# LTE.net
KiCad netlist of a schematic drawn in Altium Designer
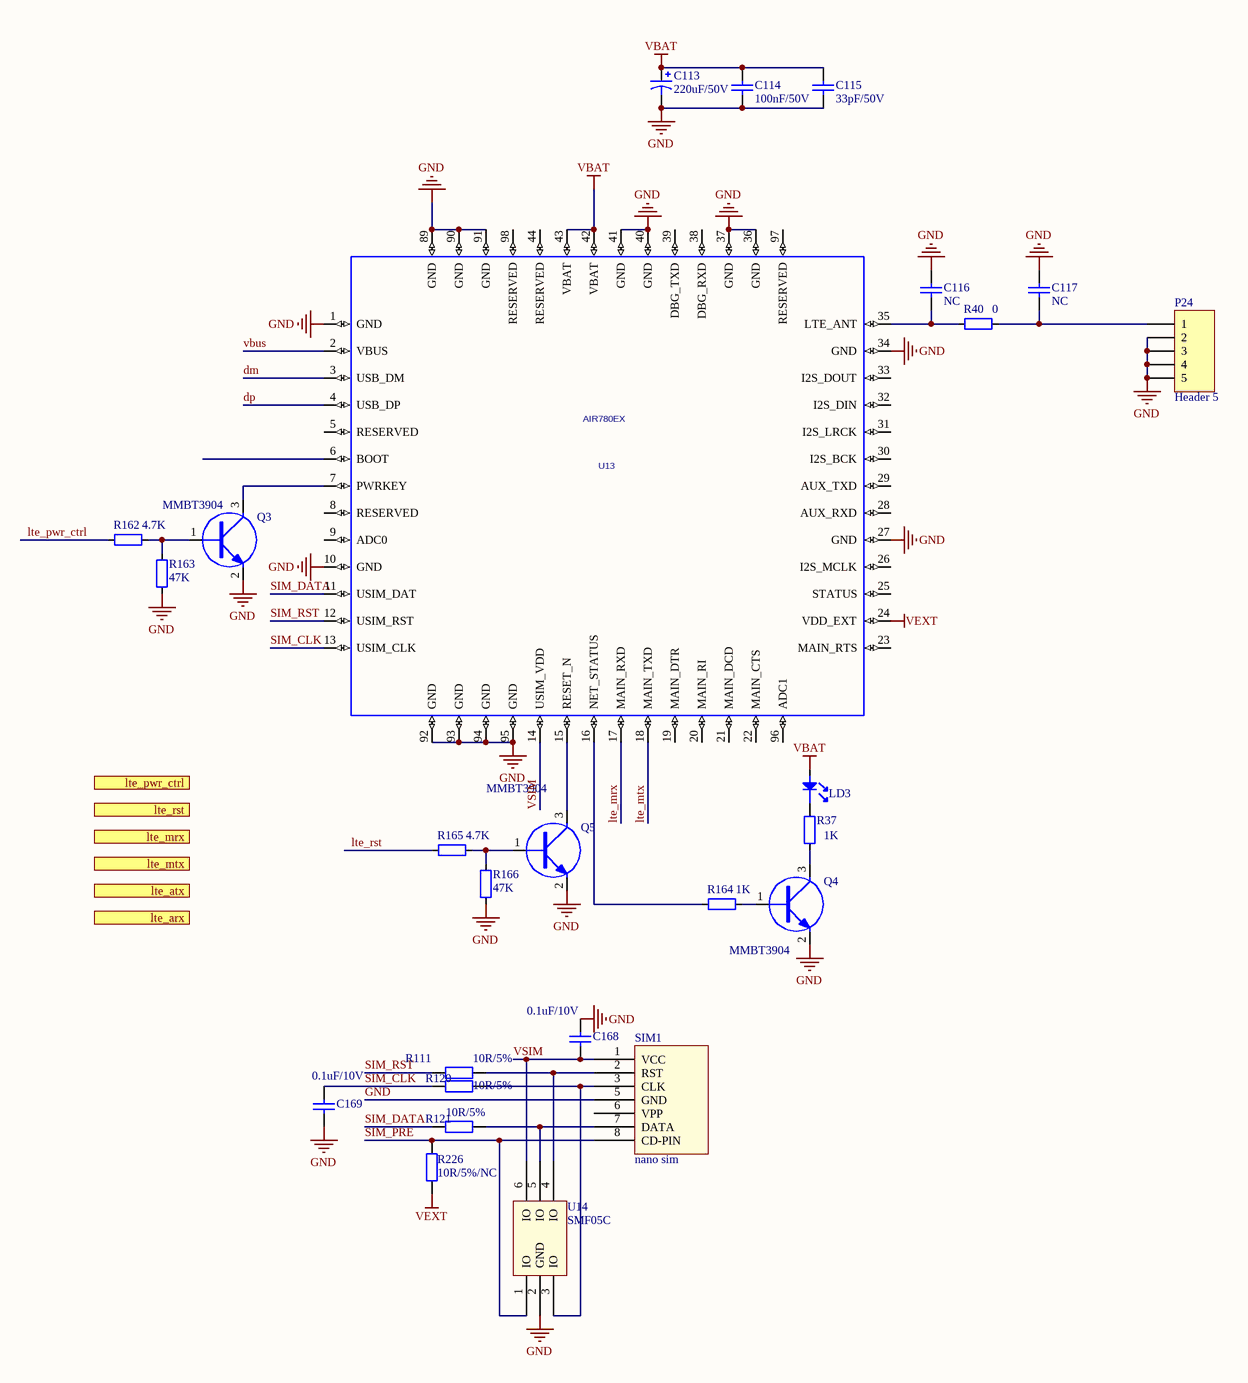
[diagram p0: LTE.SchDoc]

(export (version "E")
  (design (tool "Eeschema 10.0.6"))
  (components
    (comp (ref "C113")
      (value "220uF/50V")
      (footprint "Φ10×10")
      (description "Polarized Capacitor (Radial)")
      (fields (field (name "PUBLISHER") "Altium Limited"))
      (libsource (lib "Miscellaneous Devices") (part "Cap Pol1"))
    )
    (comp (ref "C114")
      (value "100nF/50V")
      (footprint "0603C")
      (description "Capacitor")
      (fields (field (name "PUBLISHER") "Altium Limited"))
      (libsource (lib "Miscellaneous Devices") (part "Cap"))
    )
    (comp (ref "C115")
      (value "33pF/50V")
      (footprint "0603C")
      (description "Capacitor")
      (fields (field (name "PUBLISHER") "Altium Limited"))
      (libsource (lib "Miscellaneous Devices") (part "Cap"))
    )
    (comp (ref "C116")
      (value "NC")
      (footprint "0603c")
      (description "Capacitor")
      (fields (field (name "PUBLISHER") "Altium Limited"))
      (libsource (lib "Miscellaneous Devices") (part "Cap"))
    )
    (comp (ref "C117")
      (value "NC")
      (footprint "0603c")
      (description "Capacitor")
      (fields (field (name "PUBLISHER") "Altium Limited"))
      (libsource (lib "Miscellaneous Devices") (part "Cap"))
    )
    (comp (ref "C168")
      (value "0.1uF/10V")
      (footprint "0603c")
      (description "Capacitor")
      (fields (field (name "PUBLISHER") "Altium Limited"))
      (libsource (lib "Miscellaneous Devices") (part "Cap"))
    )
    (comp (ref "C169")
      (value "0.1uF/10V")
      (footprint "0603c")
      (description "Capacitor")
      (fields (field (name "PUBLISHER") "Altium Limited"))
      (libsource (lib "Miscellaneous Devices") (part "Cap"))
    )
    (comp (ref "LD3")
      (value "LED_Green_19-217")
      (footprint "0603led")
      (libsource (lib "RC_M_D_00") (part "LED_Green_19-217"))
    )
    (comp (ref "P24")
      (value "Header 5")
      (footprint "KH-SMA-KE-Z")
      (description "Header, 5-Pin")
      (fields (field (name "PUBLISHER") "Altium Limited"))
      (libsource (lib "Miscellaneous Connectors") (part "Header 5"))
    )
    (comp (ref "Q3")
      (value "MMBT3904")
      (footprint "SOT23-3")
      (libsource (lib "CenLib") (part "NPN_MMBT3904"))
    )
    (comp (ref "Q4")
      (value "MMBT3904")
      (footprint "SOT23-3")
      (libsource (lib "CenLib") (part "NPN_MMBT3904"))
    )
    (comp (ref "Q5")
      (value "MMBT3904")
      (footprint "SOT23-3")
      (libsource (lib "CenLib") (part "NPN_MMBT3904"))
    )
    (comp (ref "R37") (value "1K") (footprint "0603R") (libsource (lib "RC_M_D_00") (part "RES0603")))
    (comp (ref "R40") (value "0") (footprint "0603r") (libsource (lib "RC_M_D_00") (part "RES0603")))
    (comp (ref "R111")
      (value "10R/5%")
      (footprint "0603r")
      (description "Resistor")
      (fields (field (name "PUBLISHER") "Altium Limited"))
      (libsource (lib "Miscellaneous Devices") (part "Res2"))
    )
    (comp (ref "R120")
      (value "10R/5%")
      (footprint "0603r")
      (description "Resistor")
      (fields (field (name "PUBLISHER") "Altium Limited"))
      (libsource (lib "Miscellaneous Devices") (part "Res2"))
    )
    (comp (ref "R121")
      (value "10R/5%")
      (footprint "0603r")
      (description "Resistor")
      (fields (field (name "PUBLISHER") "Altium Limited"))
      (libsource (lib "Miscellaneous Devices") (part "Res2"))
    )
    (comp (ref "R162") (value "4.7K") (footprint "0603R") (libsource (lib "RC_M_D_00") (part "RES0603")))
    (comp (ref "R163") (value "47K") (footprint "0603r") (libsource (lib "RC_M_D_00") (part "RES0603")))
    (comp (ref "R164") (value "1K") (footprint "0603r") (libsource (lib "RC_M_D_00") (part "RES0603")))
    (comp (ref "R165") (value "4.7K") (footprint "0603R") (libsource (lib "RC_M_D_00") (part "RES0603")))
    (comp (ref "R166") (value "47K") (footprint "0603r") (libsource (lib "RC_M_D_00") (part "RES0603")))
    (comp (ref "R226")
      (value "10R/5%/NC")
      (footprint "0603r")
      (description "Resistor")
      (fields (field (name "PUBLISHER") "Altium Limited"))
      (libsource (lib "") (part "Res2_1"))
    )
    (comp (ref "SIM1") (value "nano sim") (footprint "Nano SIM") (libsource (lib "lm") (part "nano sim")))
    (comp (ref "U13")
      (value "AIR780EX")
      (footprint "Air780EX_AD:AIR780EX")
      (libsource (lib "*") (part "AIR780EX"))
    )
    (comp (ref "U14") (value "SMF05C") (footprint "sc70-6l") (libsource (lib "lm") (part "SMF05C")))
  )
  (nets
    (net (code "1") (name "/SIM_CLK") (class "Default")
      (node (ref "C169") (pin "1") (pinfunction "1_1") (pintype "passive"))
      (node (ref "R120") (pin "2") (pinfunction "2_2") (pintype "passive"))
      (node (ref "U13") (pin "13") (pinfunction "USIM_CLK_13") (pintype "bidirectional"))
    )
    (net (code "2") (name "/SIM_DATA") (class "Default")
      (node (ref "R121") (pin "2") (pinfunction "2_2") (pintype "passive"))
      (node (ref "U13") (pin "11") (pinfunction "USIM_DAT_11") (pintype "bidirectional"))
    )
    (net (code "3") (name "/SIM_PRE") (class "Default")
      (node (ref "R226") (pin "1") (pinfunction "1_1") (pintype "passive"))
      (node (ref "SIM1") (pin "8") (pinfunction "CD-PIN_8") (pintype "passive"))
      (node (ref "U14") (pin "1") (pinfunction "IO_1") (pintype "passive"))
    )
    (net (code "4") (name "/SIM_RST") (class "Default")
      (node (ref "R111") (pin "2") (pinfunction "2_2") (pintype "passive"))
      (node (ref "U13") (pin "12") (pinfunction "USIM_RST_12") (pintype "bidirectional"))
    )
    (net (code "5") (name "/VSIM") (class "Default")
      (node (ref "C168") (pin "2") (pinfunction "2_2") (pintype "passive"))
      (node (ref "SIM1") (pin "1") (pinfunction "VCC_1") (pintype "passive"))
      (node (ref "U13") (pin "14") (pinfunction "USIM_VDD_14") (pintype "bidirectional"))
      (node (ref "U14") (pin "6") (pinfunction "IO_6") (pintype "passive"))
    )
    (net (code "6") (name "/dm") (class "Default")
      (node (ref "U13") (pin "3") (pinfunction "USB_DM_3") (pintype "bidirectional"))
    )
    (net (code "7") (name "/dp") (class "Default")
      (node (ref "U13") (pin "4") (pinfunction "USB_DP_4") (pintype "bidirectional"))
    )
    (net (code "10") (name "/lte_mrx") (class "Default")
      (node (ref "U13") (pin "17") (pinfunction "MAIN_RXD_17") (pintype "bidirectional"))
    )
    (net (code "11") (name "/lte_mtx") (class "Default")
      (node (ref "U13") (pin "18") (pinfunction "MAIN_TXD_18") (pintype "bidirectional"))
    )
    (net (code "12") (name "/lte_pwr_ctrl") (class "Default")
      (node (ref "R162") (pin "1") (pinfunction "1_1") (pintype "passive"))
    )
    (net (code "13") (name "/lte_rst") (class "Default")
      (node (ref "R165") (pin "1") (pinfunction "1_1") (pintype "passive"))
    )
    (net (code "14") (name "/vbus") (class "Default")
      (node (ref "U13") (pin "2") (pinfunction "VBUS_2") (pintype "bidirectional"))
    )
    (net (code "15") (name "GND") (class "Default")
      (node (ref "C113") (pin "2") (pinfunction "2_2") (pintype "passive"))
      (node (ref "C114") (pin "1") (pinfunction "1_1") (pintype "passive"))
      (node (ref "C115") (pin "1") (pinfunction "1_1") (pintype "passive"))
      (node (ref "C116") (pin "2") (pinfunction "2_2") (pintype "passive"))
      (node (ref "C117") (pin "2") (pinfunction "2_2") (pintype "passive"))
      (node (ref "C168") (pin "1") (pinfunction "1_1") (pintype "passive"))
      (node (ref "C169") (pin "2") (pinfunction "2_2") (pintype "passive"))
      (node (ref "P24") (pin "2") (pinfunction "2_2") (pintype "passive"))
      (node (ref "P24") (pin "3") (pinfunction "3_3") (pintype "passive"))
      (node (ref "P24") (pin "4") (pinfunction "4_4") (pintype "passive"))
      (node (ref "P24") (pin "5") (pinfunction "5_5") (pintype "passive"))
      (node (ref "Q3") (pin "2") (pinfunction "E_2") (pintype "passive"))
      (node (ref "Q4") (pin "2") (pinfunction "E_2") (pintype "passive"))
      (node (ref "Q5") (pin "2") (pinfunction "E_2") (pintype "passive"))
      (node (ref "R163") (pin "1") (pinfunction "1_1") (pintype "passive"))
      (node (ref "R166") (pin "1") (pinfunction "1_1") (pintype "passive"))
      (node (ref "SIM1") (pin "5") (pinfunction "GND_5") (pintype "passive"))
      (node (ref "U13") (pin "1") (pinfunction "GND_1") (pintype "bidirectional"))
      (node (ref "U13") (pin "10") (pinfunction "GND_10") (pintype "bidirectional"))
      (node (ref "U13") (pin "27") (pinfunction "GND_27") (pintype "bidirectional"))
      (node (ref "U13") (pin "34") (pinfunction "GND_34") (pintype "bidirectional"))
      (node (ref "U13") (pin "36") (pinfunction "GND_36") (pintype "bidirectional"))
      (node (ref "U13") (pin "37") (pinfunction "GND_37") (pintype "bidirectional"))
      (node (ref "U13") (pin "40") (pinfunction "GND_40") (pintype "bidirectional"))
      (node (ref "U13") (pin "41") (pinfunction "GND_41") (pintype "bidirectional"))
      (node (ref "U13") (pin "89") (pinfunction "GND_89") (pintype "bidirectional"))
      (node (ref "U13") (pin "90") (pinfunction "GND_90") (pintype "bidirectional"))
      (node (ref "U13") (pin "91") (pinfunction "GND_91") (pintype "bidirectional"))
      (node (ref "U13") (pin "92") (pinfunction "GND_92") (pintype "bidirectional"))
      (node (ref "U13") (pin "93") (pinfunction "GND_93") (pintype "bidirectional"))
      (node (ref "U13") (pin "94") (pinfunction "GND_94") (pintype "bidirectional"))
      (node (ref "U13") (pin "95") (pinfunction "GND_95") (pintype "bidirectional"))
      (node (ref "U14") (pin "2") (pinfunction "GND_2") (pintype "passive"))
    )
    (net (code "16") (name "Net-(C117-Pad1)") (class "Default")
      (node (ref "C117") (pin "1") (pinfunction "1_1") (pintype "passive"))
      (node (ref "P24") (pin "1") (pinfunction "1_1") (pintype "passive"))
      (node (ref "R40") (pin "2") (pinfunction "2_2") (pintype "passive"))
    )
    (net (code "17") (name "Net-(LD3-Pad2)") (class "Default")
      (node (ref "LD3") (pin "2") (pinfunction "2_2") (pintype "passive"))
      (node (ref "R37") (pin "1") (pinfunction "1_1") (pintype "passive"))
    )
    (net (code "18") (name "Net-(Q3-B)") (class "Default")
      (node (ref "Q3") (pin "1") (pinfunction "B_1") (pintype "passive"))
      (node (ref "R162") (pin "2") (pinfunction "2_2") (pintype "passive"))
      (node (ref "R163") (pin "2") (pinfunction "2_2") (pintype "passive"))
    )
    (net (code "19") (name "Net-(Q3-C)") (class "Default")
      (node (ref "Q3") (pin "3") (pinfunction "C_3") (pintype "passive"))
      (node (ref "U13") (pin "7") (pinfunction "PWRKEY_7") (pintype "bidirectional"))
    )
    (net (code "20") (name "Net-(Q4-B)") (class "Default")
      (node (ref "Q4") (pin "1") (pinfunction "B_1") (pintype "passive"))
      (node (ref "R164") (pin "2") (pinfunction "2_2") (pintype "passive"))
    )
    (net (code "21") (name "Net-(Q4-C)") (class "Default")
      (node (ref "Q4") (pin "3") (pinfunction "C_3") (pintype "passive"))
      (node (ref "R37") (pin "2") (pinfunction "2_2") (pintype "passive"))
    )
    (net (code "22") (name "Net-(Q5-B)") (class "Default")
      (node (ref "Q5") (pin "1") (pinfunction "B_1") (pintype "passive"))
      (node (ref "R165") (pin "2") (pinfunction "2_2") (pintype "passive"))
      (node (ref "R166") (pin "2") (pinfunction "2_2") (pintype "passive"))
    )
    (net (code "23") (name "Net-(Q5-C)") (class "Default")
      (node (ref "Q5") (pin "3") (pinfunction "C_3") (pintype "passive"))
      (node (ref "U13") (pin "15") (pinfunction "RESET_N_15") (pintype "bidirectional"))
    )
    (net (code "24") (name "Net-(SIM1-CLK)") (class "Default")
      (node (ref "R120") (pin "1") (pinfunction "1_1") (pintype "passive"))
      (node (ref "SIM1") (pin "3") (pinfunction "CLK_3") (pintype "passive"))
      (node (ref "U14") (pin "3") (pinfunction "IO_3") (pintype "passive"))
    )
    (net (code "25") (name "Net-(SIM1-DATA)") (class "Default")
      (node (ref "R121") (pin "1") (pinfunction "1_1") (pintype "passive"))
      (node (ref "SIM1") (pin "7") (pinfunction "DATA_7") (pintype "passive"))
      (node (ref "U14") (pin "5") (pinfunction "IO_5") (pintype "passive"))
    )
    (net (code "26") (name "Net-(SIM1-RST)") (class "Default")
      (node (ref "R111") (pin "1") (pinfunction "1_1") (pintype "passive"))
      (node (ref "SIM1") (pin "2") (pinfunction "RST_2") (pintype "passive"))
      (node (ref "U14") (pin "4") (pinfunction "IO_4") (pintype "passive"))
    )
    (net (code "27") (name "Net-(U13-LTE_ANT)") (class "Default")
      (node (ref "C116") (pin "1") (pinfunction "1_1") (pintype "passive"))
      (node (ref "R40") (pin "1") (pinfunction "1_1") (pintype "passive"))
      (node (ref "U13") (pin "35") (pinfunction "LTE_ANT_35") (pintype "bidirectional"))
    )
    (net (code "28") (name "Net-(U13-NET_STATUS)") (class "Default")
      (node (ref "R164") (pin "1") (pinfunction "1_1") (pintype "passive"))
      (node (ref "U13") (pin "16") (pinfunction "NET_STATUS_16") (pintype "bidirectional"))
    )
    (net (code "29") (name "VBAT") (class "Default")
      (node (ref "C113") (pin "1") (pinfunction "1_1") (pintype "passive"))
      (node (ref "C114") (pin "2") (pinfunction "2_2") (pintype "passive"))
      (node (ref "C115") (pin "2") (pinfunction "2_2") (pintype "passive"))
      (node (ref "LD3") (pin "1") (pinfunction "1_1") (pintype "passive"))
      (node (ref "U13") (pin "42") (pinfunction "VBAT_42") (pintype "bidirectional"))
      (node (ref "U13") (pin "43") (pinfunction "VBAT_43") (pintype "bidirectional"))
    )
    (net (code "30") (name "VEXT") (class "Default")
      (node (ref "R226") (pin "2") (pinfunction "2_2") (pintype "passive"))
      (node (ref "U13") (pin "24") (pinfunction "VDD_EXT_24") (pintype "bidirectional"))
    )
    (net (code "31") (name "unconnected-(SIM1-VPP-Pad6)") (class "Default")
      (node (ref "SIM1") (pin "6") (pinfunction "VPP_6") (pintype "passive"))
    )
    (net (code "32") (name "unconnected-(U13-ADC0-Pad9)") (class "Default")
      (node (ref "U13") (pin "9") (pinfunction "ADC0_9") (pintype "bidirectional"))
    )
    (net (code "33") (name "unconnected-(U13-ADC1-Pad96)") (class "Default")
      (node (ref "U13") (pin "96") (pinfunction "ADC1_96") (pintype "bidirectional"))
    )
    (net (code "34") (name "unconnected-(U13-AUX_RXD-Pad28)") (class "Default")
      (node (ref "U13") (pin "28") (pinfunction "AUX_RXD_28") (pintype "bidirectional"))
    )
    (net (code "35") (name "unconnected-(U13-AUX_TXD-Pad29)") (class "Default")
      (node (ref "U13") (pin "29") (pinfunction "AUX_TXD_29") (pintype "bidirectional"))
    )
    (net (code "36") (name "unconnected-(U13-BOOT-Pad6)") (class "Default")
      (node (ref "U13") (pin "6") (pinfunction "BOOT_6") (pintype "bidirectional"))
    )
    (net (code "37") (name "unconnected-(U13-DBG_RXD-Pad38)") (class "Default")
      (node (ref "U13") (pin "38") (pinfunction "DBG_RXD_38") (pintype "bidirectional"))
    )
    (net (code "38") (name "unconnected-(U13-DBG_TXD-Pad39)") (class "Default")
      (node (ref "U13") (pin "39") (pinfunction "DBG_TXD_39") (pintype "bidirectional"))
    )
    (net (code "39") (name "unconnected-(U13-I2S_BCK-Pad30)") (class "Default")
      (node (ref "U13") (pin "30") (pinfunction "I2S_BCK_30") (pintype "bidirectional"))
    )
    (net (code "40") (name "unconnected-(U13-I2S_DIN-Pad32)") (class "Default")
      (node (ref "U13") (pin "32") (pinfunction "I2S_DIN_32") (pintype "bidirectional"))
    )
    (net (code "41") (name "unconnected-(U13-I2S_DOUT-Pad33)") (class "Default")
      (node (ref "U13") (pin "33") (pinfunction "I2S_DOUT_33") (pintype "bidirectional"))
    )
    (net (code "42") (name "unconnected-(U13-I2S_LRCK-Pad31)") (class "Default")
      (node (ref "U13") (pin "31") (pinfunction "I2S_LRCK_31") (pintype "bidirectional"))
    )
    (net (code "43") (name "unconnected-(U13-I2S_MCLK-Pad26)") (class "Default")
      (node (ref "U13") (pin "26") (pinfunction "I2S_MCLK_26") (pintype "bidirectional"))
    )
    (net (code "44") (name "unconnected-(U13-MAIN_CTS-Pad22)") (class "Default")
      (node (ref "U13") (pin "22") (pinfunction "MAIN_CTS_22") (pintype "bidirectional"))
    )
    (net (code "45") (name "unconnected-(U13-MAIN_DCD-Pad21)") (class "Default")
      (node (ref "U13") (pin "21") (pinfunction "MAIN_DCD_21") (pintype "bidirectional"))
    )
    (net (code "46") (name "unconnected-(U13-MAIN_DTR-Pad19)") (class "Default")
      (node (ref "U13") (pin "19") (pinfunction "MAIN_DTR_19") (pintype "bidirectional"))
    )
    (net (code "47") (name "unconnected-(U13-MAIN_RI-Pad20)") (class "Default")
      (node (ref "U13") (pin "20") (pinfunction "MAIN_RI_20") (pintype "bidirectional"))
    )
    (net (code "48") (name "unconnected-(U13-MAIN_RTS-Pad23)") (class "Default")
      (node (ref "U13") (pin "23") (pinfunction "MAIN_RTS_23") (pintype "bidirectional"))
    )
    (net (code "49") (name "unconnected-(U13-RESERVED-Pad5)") (class "Default")
      (node (ref "U13") (pin "5") (pinfunction "RESERVED_5") (pintype "bidirectional"))
    )
    (net (code "50") (name "unconnected-(U13-RESERVED-Pad8)") (class "Default")
      (node (ref "U13") (pin "8") (pinfunction "RESERVED_8") (pintype "bidirectional"))
    )
    (net (code "51") (name "unconnected-(U13-RESERVED-Pad44)") (class "Default")
      (node (ref "U13") (pin "44") (pinfunction "RESERVED_44") (pintype "bidirectional"))
    )
    (net (code "52") (name "unconnected-(U13-RESERVED-Pad97)") (class "Default")
      (node (ref "U13") (pin "97") (pinfunction "RESERVED_97") (pintype "bidirectional"))
    )
    (net (code "53") (name "unconnected-(U13-RESERVED-Pad98)") (class "Default")
      (node (ref "U13") (pin "98") (pinfunction "RESERVED_98") (pintype "bidirectional"))
    )
    (net (code "54") (name "unconnected-(U13-STATUS-Pad25)") (class "Default")
      (node (ref "U13") (pin "25") (pinfunction "STATUS_25") (pintype "bidirectional"))
    )
  )
)
